# Peripherals.net
KiCad netlist of a schematic drawn in Altium Designer
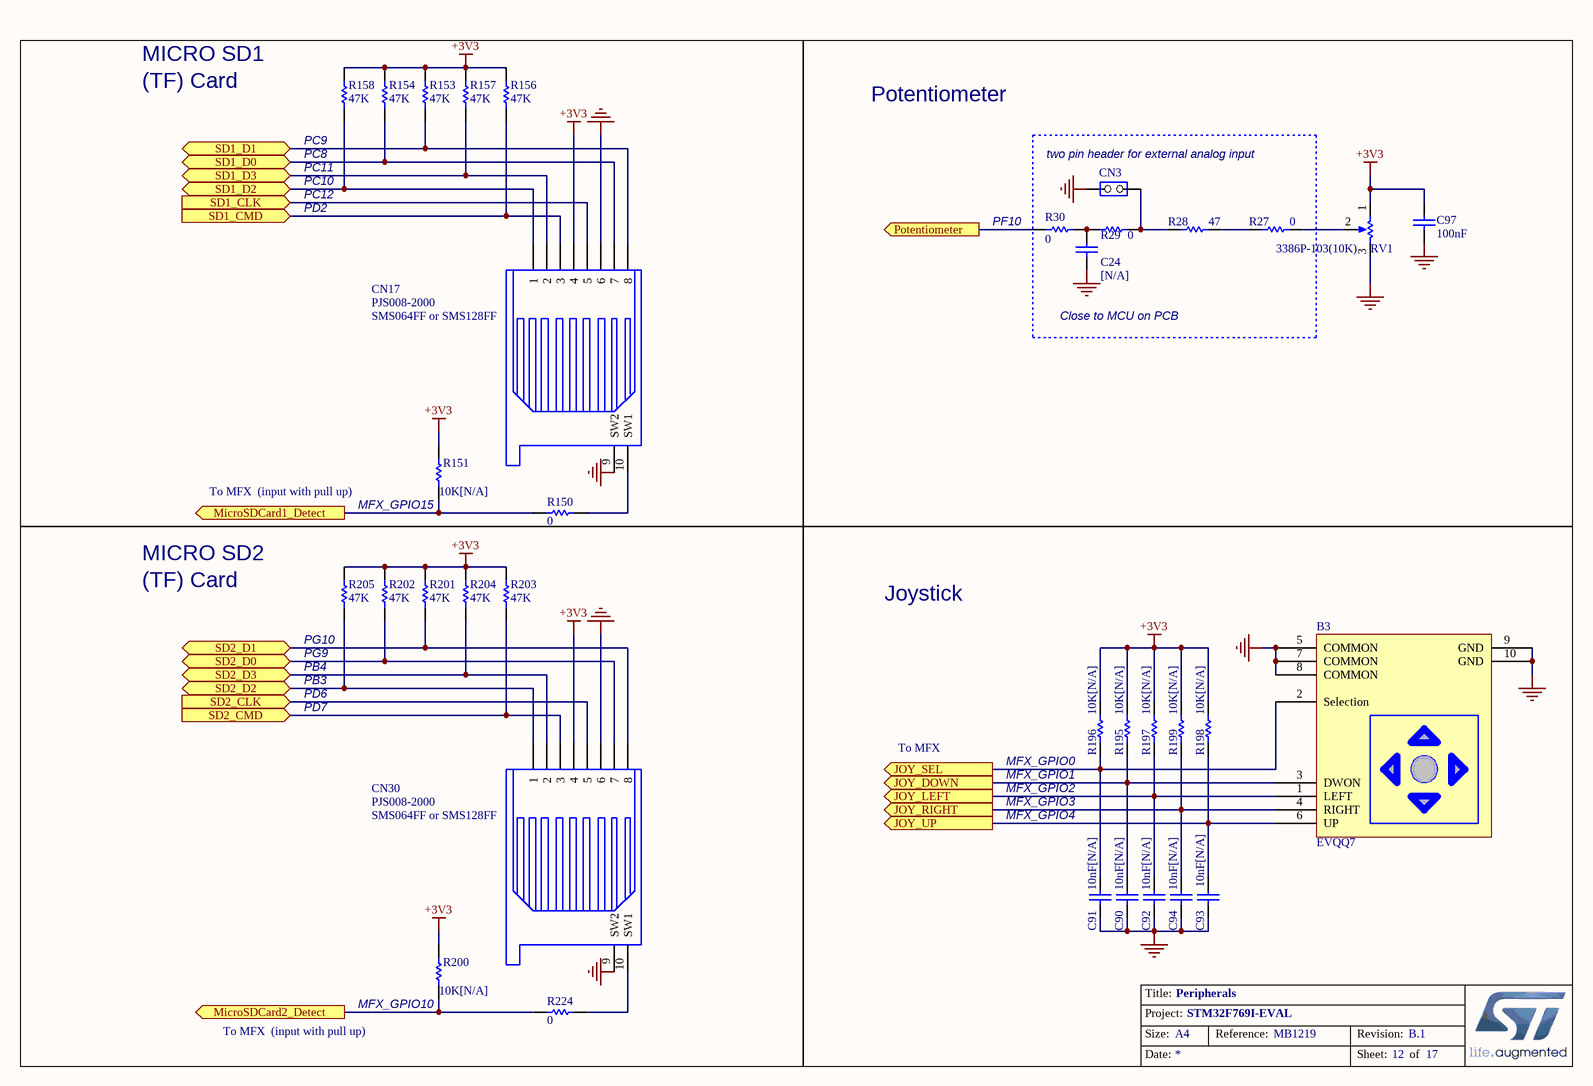
[diagram p0: Peripherals.SchDoc]

(export (version "E")
  (design (tool "Eeschema 10.0.6"))
  (components
    (comp (ref "B3") (value "EVQQ7") (footprint "SW-JOY") (libsource (lib "mb1045") (part "EVQQ7")))
    (comp (ref "C24")
      (value "[N/A]")
      (footprint "0603C")
      (description "Capacitor")
      (fields (field (name "PUBLISHER") "Altium Limited"))
      (libsource (lib "Miscellaneous Devices") (part "cap"))
    )
    (comp (ref "C90")
      (value "10nF[N/A]")
      (footprint "0603C")
      (description "Capacitor")
      (fields (field (name "PUBLISHER") "Altium Limited"))
      (libsource (lib "Miscellaneous Devices") (part "CAP"))
    )
    (comp (ref "C91")
      (value "10nF[N/A]")
      (footprint "0603C")
      (description "Capacitor")
      (fields (field (name "PUBLISHER") "Altium Limited"))
      (libsource (lib "Miscellaneous Devices") (part "CAP"))
    )
    (comp (ref "C92")
      (value "10nF[N/A]")
      (footprint "0603C")
      (description "Capacitor")
      (fields (field (name "PUBLISHER") "Altium Limited"))
      (libsource (lib "Miscellaneous Devices") (part "CAP"))
    )
    (comp (ref "C93")
      (value "10nF[N/A]")
      (footprint "0603C")
      (description "Capacitor")
      (fields (field (name "PUBLISHER") "Altium Limited"))
      (libsource (lib "Miscellaneous Devices") (part "CAP"))
    )
    (comp (ref "C94")
      (value "10nF[N/A]")
      (footprint "0603C")
      (description "Capacitor")
      (fields (field (name "PUBLISHER") "Altium Limited"))
      (libsource (lib "Miscellaneous Devices") (part "CAP"))
    )
    (comp (ref "C97")
      (value "100nF")
      (footprint "0603C")
      (description "Capacitor")
      (fields (field (name "PUBLISHER") "Altium Limited"))
      (libsource (lib "Miscellaneous Devices") (part "CAP"))
    )
    (comp (ref "CN3") (value "~") (footprint "SIP2") (libsource (lib "*") (part "JP2")))
    (comp (ref "CN17")
      (value "PJS008-2000")
      (footprint "MSD_PJS008_")
      (libsource (lib "MB525") (part "SMS016AFA5E"))
    )
    (comp (ref "CN30")
      (value "PJS008-2000")
      (footprint "MSD_PJS008_")
      (libsource (lib "MB525") (part "SMS016AFA5E"))
    )
    (comp (ref "R27")
      (value "0")
      (footprint "0603R")
      (description "Resistor")
      (fields (field (name "PUBLISHER") "Altium Limited"))
      (libsource (lib "Miscellaneous Devices") (part "Res1"))
    )
    (comp (ref "R28")
      (value "47")
      (footprint "0603R")
      (description "Resistor")
      (fields (field (name "PUBLISHER") "Altium Limited"))
      (libsource (lib "Miscellaneous Devices") (part "Res1"))
    )
    (comp (ref "R29")
      (value "0")
      (footprint "0603R")
      (description "Resistor")
      (fields (field (name "PUBLISHER") "Altium Limited"))
      (libsource (lib "Miscellaneous Devices") (part "Res1"))
    )
    (comp (ref "R30")
      (value "0")
      (footprint "0603R")
      (description "Resistor")
      (fields (field (name "PUBLISHER") "Altium Limited"))
      (libsource (lib "Miscellaneous Devices") (part "Res1"))
    )
    (comp (ref "R150")
      (value "0")
      (footprint "0603R")
      (description "Resistor")
      (fields (field (name "PUBLISHER") "Altium Limited"))
      (libsource (lib "Miscellaneous Devices") (part "Res1"))
    )
    (comp (ref "R151")
      (value "10K[N/A]")
      (footprint "0603R")
      (description "Resistor")
      (fields (field (name "PUBLISHER") "Altium Limited"))
      (libsource (lib "Miscellaneous Devices") (part "Res1"))
    )
    (comp (ref "R153")
      (value "47K")
      (footprint "0603R")
      (description "Resistor")
      (fields (field (name "PUBLISHER") "Altium Limited"))
      (libsource (lib "Miscellaneous Devices") (part "res1"))
    )
    (comp (ref "R154")
      (value "47K")
      (footprint "0603R")
      (description "Resistor")
      (fields (field (name "PUBLISHER") "Altium Limited"))
      (libsource (lib "Miscellaneous Devices") (part "res1"))
    )
    (comp (ref "R156")
      (value "47K")
      (footprint "0603R")
      (description "Resistor")
      (fields (field (name "PUBLISHER") "Altium Limited"))
      (libsource (lib "Miscellaneous Devices") (part "res1"))
    )
    (comp (ref "R157")
      (value "47K")
      (footprint "0603R")
      (description "Resistor")
      (fields (field (name "PUBLISHER") "Altium Limited"))
      (libsource (lib "Miscellaneous Devices") (part "res1"))
    )
    (comp (ref "R158")
      (value "47K")
      (footprint "0603R")
      (description "Resistor")
      (fields (field (name "PUBLISHER") "Altium Limited"))
      (libsource (lib "Miscellaneous Devices") (part "res1"))
    )
    (comp (ref "R195")
      (value "10K[N/A]")
      (footprint "0603R")
      (description "Resistor")
      (fields (field (name "PUBLISHER") "Altium Limited"))
      (libsource (lib "Miscellaneous Devices") (part "res1"))
    )
    (comp (ref "R196")
      (value "10K[N/A]")
      (footprint "0603R")
      (description "Resistor")
      (fields (field (name "PUBLISHER") "Altium Limited"))
      (libsource (lib "Miscellaneous Devices") (part "res1"))
    )
    (comp (ref "R197")
      (value "10K[N/A]")
      (footprint "0603R")
      (description "Resistor")
      (fields (field (name "PUBLISHER") "Altium Limited"))
      (libsource (lib "Miscellaneous Devices") (part "res1"))
    )
    (comp (ref "R198")
      (value "10K[N/A]")
      (footprint "0603R")
      (description "Resistor")
      (fields (field (name "PUBLISHER") "Altium Limited"))
      (libsource (lib "Miscellaneous Devices") (part "res1"))
    )
    (comp (ref "R199")
      (value "10K[N/A]")
      (footprint "0603R")
      (description "Resistor")
      (fields (field (name "PUBLISHER") "Altium Limited"))
      (libsource (lib "Miscellaneous Devices") (part "res1"))
    )
    (comp (ref "R200")
      (value "10K[N/A]")
      (footprint "0603R")
      (description "Resistor")
      (fields (field (name "PUBLISHER") "Altium Limited"))
      (libsource (lib "Miscellaneous Devices") (part "Res1"))
    )
    (comp (ref "R201")
      (value "47K")
      (footprint "0603R")
      (description "Resistor")
      (fields (field (name "PUBLISHER") "Altium Limited"))
      (libsource (lib "Miscellaneous Devices") (part "res1"))
    )
    (comp (ref "R202")
      (value "47K")
      (footprint "0603R")
      (description "Resistor")
      (fields (field (name "PUBLISHER") "Altium Limited"))
      (libsource (lib "Miscellaneous Devices") (part "res1"))
    )
    (comp (ref "R203")
      (value "47K")
      (footprint "0603R")
      (description "Resistor")
      (fields (field (name "PUBLISHER") "Altium Limited"))
      (libsource (lib "Miscellaneous Devices") (part "res1"))
    )
    (comp (ref "R204")
      (value "47K")
      (footprint "0603R")
      (description "Resistor")
      (fields (field (name "PUBLISHER") "Altium Limited"))
      (libsource (lib "Miscellaneous Devices") (part "res1"))
    )
    (comp (ref "R205")
      (value "47K")
      (footprint "0603R")
      (description "Resistor")
      (fields (field (name "PUBLISHER") "Altium Limited"))
      (libsource (lib "Miscellaneous Devices") (part "res1"))
    )
    (comp (ref "R224")
      (value "0")
      (footprint "0603R")
      (description "Resistor")
      (fields (field (name "PUBLISHER") "Altium Limited"))
      (libsource (lib "Miscellaneous Devices") (part "Res1"))
    )
    (comp (ref "RV1")
      (value "3386P-103(10K)")
      (footprint "3386P")
      (libsource (lib "STR910_SCHLIB") (part "RV"))
    )
  )
  (nets
    (net (code "1") (name "+3V3") (class "Default")
      (node (ref "C97") (pin "1") (pinfunction "1_1") (pintype "passive"))
      (node (ref "CN17") (pin "4") (pinfunction "4_4") (pintype "passive"))
      (node (ref "CN30") (pin "4") (pinfunction "4_4") (pintype "passive"))
      (node (ref "R151") (pin "2") (pinfunction "2_2") (pintype "passive"))
      (node (ref "R153") (pin "1") (pinfunction "1_1") (pintype "passive"))
      (node (ref "R154") (pin "1") (pinfunction "1_1") (pintype "passive"))
      (node (ref "R156") (pin "1") (pinfunction "1_1") (pintype "passive"))
      (node (ref "R157") (pin "1") (pinfunction "1_1") (pintype "passive"))
      (node (ref "R158") (pin "1") (pinfunction "1_1") (pintype "passive"))
      (node (ref "R195") (pin "1") (pinfunction "1_1") (pintype "passive"))
      (node (ref "R196") (pin "1") (pinfunction "1_1") (pintype "passive"))
      (node (ref "R197") (pin "1") (pinfunction "1_1") (pintype "passive"))
      (node (ref "R198") (pin "1") (pinfunction "1_1") (pintype "passive"))
      (node (ref "R199") (pin "1") (pinfunction "1_1") (pintype "passive"))
      (node (ref "R200") (pin "2") (pinfunction "2_2") (pintype "passive"))
      (node (ref "R201") (pin "1") (pinfunction "1_1") (pintype "passive"))
      (node (ref "R202") (pin "1") (pinfunction "1_1") (pintype "passive"))
      (node (ref "R203") (pin "1") (pinfunction "1_1") (pintype "passive"))
      (node (ref "R204") (pin "1") (pinfunction "1_1") (pintype "passive"))
      (node (ref "R205") (pin "1") (pinfunction "1_1") (pintype "passive"))
      (node (ref "RV1") (pin "1") (pinfunction "BOT_1") (pintype "passive"))
    )
    (net (code "2") (name "/JOY_DOWN") (class "Default")
      (node (ref "B3") (pin "3") (pinfunction "DWON_3") (pintype "passive"))
      (node (ref "C90") (pin "2") (pinfunction "2_2") (pintype "passive"))
      (node (ref "R195") (pin "2") (pinfunction "2_2") (pintype "passive"))
    )
    (net (code "3") (name "/JOY_LEFT") (class "Default")
      (node (ref "B3") (pin "1") (pinfunction "LEFT_1") (pintype "passive"))
      (node (ref "C92") (pin "2") (pinfunction "2_2") (pintype "passive"))
      (node (ref "R197") (pin "2") (pinfunction "2_2") (pintype "passive"))
    )
    (net (code "4") (name "/JOY_RIGHT") (class "Default")
      (node (ref "B3") (pin "4") (pinfunction "RIGHT_4") (pintype "passive"))
      (node (ref "C94") (pin "2") (pinfunction "2_2") (pintype "passive"))
      (node (ref "R199") (pin "2") (pinfunction "2_2") (pintype "passive"))
    )
    (net (code "5") (name "/JOY_SEL") (class "Default")
      (node (ref "B3") (pin "2") (pinfunction "Selection_2") (pintype "passive"))
      (node (ref "C91") (pin "2") (pinfunction "2_2") (pintype "passive"))
      (node (ref "R196") (pin "2") (pinfunction "2_2") (pintype "passive"))
    )
    (net (code "6") (name "/JOY_UP") (class "Default")
      (node (ref "B3") (pin "6") (pinfunction "UP_6") (pintype "passive"))
      (node (ref "C93") (pin "2") (pinfunction "2_2") (pintype "passive"))
      (node (ref "R198") (pin "2") (pinfunction "2_2") (pintype "passive"))
    )
    (net (code "7") (name "/MicroSDCard1_Detect") (class "Default")
      (node (ref "R150") (pin "1") (pinfunction "1_1") (pintype "passive"))
      (node (ref "R151") (pin "1") (pinfunction "1_1") (pintype "passive"))
    )
    (net (code "8") (name "/MicroSDCard2_Detect") (class "Default")
      (node (ref "R200") (pin "1") (pinfunction "1_1") (pintype "passive"))
      (node (ref "R224") (pin "1") (pinfunction "1_1") (pintype "passive"))
    )
    (net (code "9") (name "/Potentiometer") (class "Default")
      (node (ref "R30") (pin "2") (pinfunction "2_2") (pintype "passive"))
    )
    (net (code "10") (name "/SD1_CLK") (class "Default")
      (node (ref "CN17") (pin "5") (pinfunction "5_5") (pintype "passive"))
    )
    (net (code "11") (name "/SD1_CMD") (class "Default")
      (node (ref "CN17") (pin "3") (pinfunction "3_3") (pintype "passive"))
      (node (ref "R156") (pin "2") (pinfunction "2_2") (pintype "passive"))
    )
    (net (code "12") (name "/SD1_D0") (class "Default")
      (node (ref "CN17") (pin "7") (pinfunction "7_7") (pintype "passive"))
      (node (ref "R154") (pin "2") (pinfunction "2_2") (pintype "passive"))
    )
    (net (code "13") (name "/SD1_D1") (class "Default")
      (node (ref "CN17") (pin "8") (pinfunction "8_8") (pintype "passive"))
      (node (ref "R153") (pin "2") (pinfunction "2_2") (pintype "passive"))
    )
    (net (code "14") (name "/SD1_D2") (class "Default")
      (node (ref "CN17") (pin "1") (pinfunction "1_1") (pintype "passive"))
      (node (ref "R158") (pin "2") (pinfunction "2_2") (pintype "passive"))
    )
    (net (code "15") (name "/SD1_D3") (class "Default")
      (node (ref "CN17") (pin "2") (pinfunction "2_2") (pintype "passive"))
      (node (ref "R157") (pin "2") (pinfunction "2_2") (pintype "passive"))
    )
    (net (code "16") (name "/SD2_CLK") (class "Default")
      (node (ref "CN30") (pin "5") (pinfunction "5_5") (pintype "passive"))
    )
    (net (code "17") (name "/SD2_CMD") (class "Default")
      (node (ref "CN30") (pin "3") (pinfunction "3_3") (pintype "passive"))
      (node (ref "R203") (pin "2") (pinfunction "2_2") (pintype "passive"))
    )
    (net (code "18") (name "/SD2_D0") (class "Default")
      (node (ref "CN30") (pin "7") (pinfunction "7_7") (pintype "passive"))
      (node (ref "R202") (pin "2") (pinfunction "2_2") (pintype "passive"))
    )
    (net (code "19") (name "/SD2_D1") (class "Default")
      (node (ref "CN30") (pin "8") (pinfunction "8_8") (pintype "passive"))
      (node (ref "R201") (pin "2") (pinfunction "2_2") (pintype "passive"))
    )
    (net (code "20") (name "/SD2_D2") (class "Default")
      (node (ref "CN30") (pin "1") (pinfunction "1_1") (pintype "passive"))
      (node (ref "R205") (pin "2") (pinfunction "2_2") (pintype "passive"))
    )
    (net (code "21") (name "/SD2_D3") (class "Default")
      (node (ref "CN30") (pin "2") (pinfunction "2_2") (pintype "passive"))
      (node (ref "R204") (pin "2") (pinfunction "2_2") (pintype "passive"))
    )
    (net (code "22") (name "GND") (class "Default")
      (node (ref "B3") (pin "10") (pinfunction "GND_10") (pintype "passive"))
      (node (ref "B3") (pin "5") (pinfunction "COMMON_5") (pintype "passive"))
      (node (ref "B3") (pin "7") (pinfunction "COMMON_7") (pintype "passive"))
      (node (ref "B3") (pin "8") (pinfunction "COMMON_8") (pintype "passive"))
      (node (ref "B3") (pin "9") (pinfunction "GND_9") (pintype "passive"))
      (node (ref "C24") (pin "1") (pinfunction "1_1") (pintype "passive"))
      (node (ref "C90") (pin "1") (pinfunction "1_1") (pintype "passive"))
      (node (ref "C91") (pin "1") (pinfunction "1_1") (pintype "passive"))
      (node (ref "C92") (pin "1") (pinfunction "1_1") (pintype "passive"))
      (node (ref "C93") (pin "1") (pinfunction "1_1") (pintype "passive"))
      (node (ref "C94") (pin "1") (pinfunction "1_1") (pintype "passive"))
      (node (ref "C97") (pin "2") (pinfunction "2_2") (pintype "passive"))
      (node (ref "CN17") (pin "6") (pinfunction "6_6") (pintype "passive"))
      (node (ref "CN17") (pin "9") (pinfunction "SW2_9") (pintype "passive"))
      (node (ref "CN3") (pin "2") (pinfunction "NO_2") (pintype "passive"))
      (node (ref "CN30") (pin "6") (pinfunction "6_6") (pintype "passive"))
      (node (ref "CN30") (pin "9") (pinfunction "SW2_9") (pintype "passive"))
      (node (ref "RV1") (pin "3") (pinfunction "TOP_3") (pintype "passive"))
    )
    (net (code "23") (name "Net-(C24-Pad2)") (class "Default")
      (node (ref "C24") (pin "2") (pinfunction "2_2") (pintype "passive"))
      (node (ref "R29") (pin "1") (pinfunction "1_1") (pintype "passive"))
      (node (ref "R30") (pin "1") (pinfunction "1_1") (pintype "passive"))
    )
    (net (code "24") (name "Net-(CN3-COMMON)") (class "Default")
      (node (ref "CN3") (pin "1") (pinfunction "COMMON_1") (pintype "passive"))
      (node (ref "R28") (pin "1") (pinfunction "1_1") (pintype "passive"))
      (node (ref "R29") (pin "2") (pinfunction "2_2") (pintype "passive"))
    )
    (net (code "25") (name "Net-(CN17-SW1)") (class "Default")
      (node (ref "CN17") (pin "10") (pinfunction "SW1_10") (pintype "passive"))
      (node (ref "R150") (pin "2") (pinfunction "2_2") (pintype "passive"))
    )
    (net (code "26") (name "Net-(CN30-SW1)") (class "Default")
      (node (ref "CN30") (pin "10") (pinfunction "SW1_10") (pintype "passive"))
      (node (ref "R224") (pin "2") (pinfunction "2_2") (pintype "passive"))
    )
    (net (code "27") (name "Net-(R27-Pad1)") (class "Default")
      (node (ref "R27") (pin "1") (pinfunction "1_1") (pintype "passive"))
      (node (ref "R28") (pin "2") (pinfunction "2_2") (pintype "passive"))
    )
    (net (code "28") (name "Net-(RV1-TAP)") (class "Default")
      (node (ref "R27") (pin "2") (pinfunction "2_2") (pintype "passive"))
      (node (ref "RV1") (pin "2") (pinfunction "TAP_2") (pintype "passive"))
    )
  )
)
